# keyboard-Left.net
KiCad netlist of a schematic drawn in Altium Designer
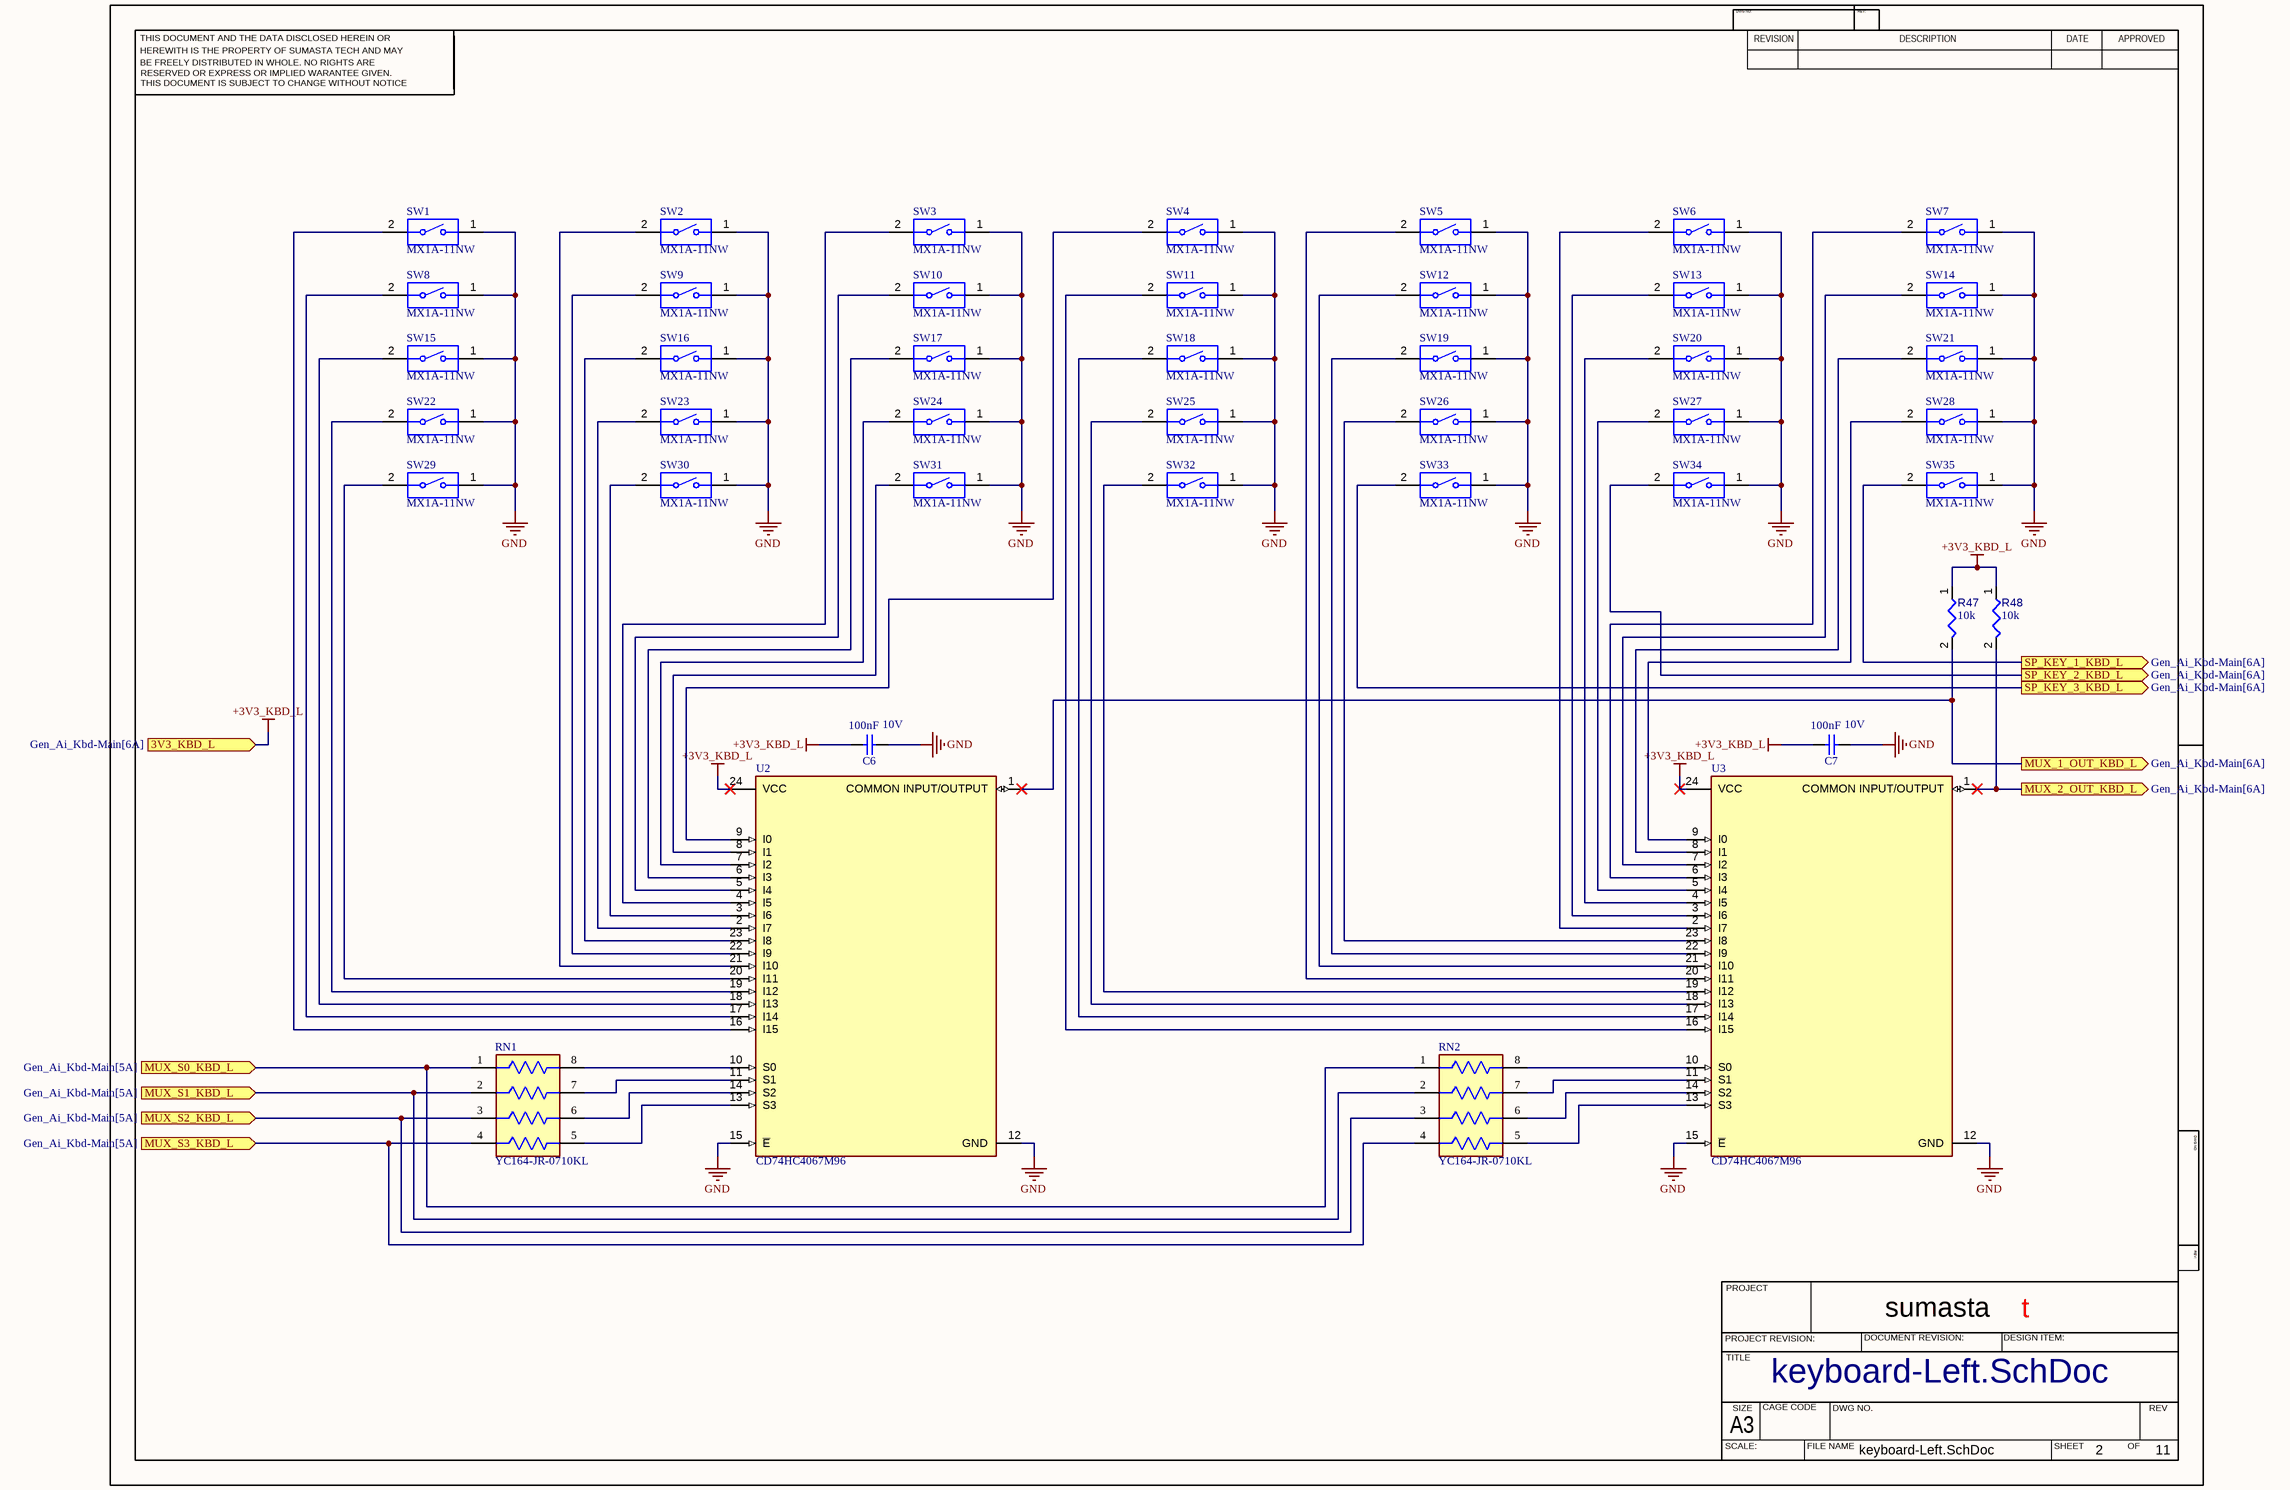
[diagram p0: keyboard-Left.SchDoc]

(export (version "E")
  (design (tool "Eeschema 10.0.6"))
  (components
    (comp (ref "C6")
      (value "885012206020")
      (footprint "WCAP-CSGP_0603_L1.6W0.8H0.8_Reflow")
      (description "WCAP-CSGP Multilayer Ceramic Chip Capacitor, General Purpose, size 0603, X7R, 100nF, 10VDC")
      (fields
        (field (name "MANUFACTURER") "Wurth Elektronik")
        (field (name "RATED VOLTAGE (DC)") "10V")
        (field (name "CAPACITANCE") "100nF")
      )
      (libsource (lib "Test365") (part "885012209047R"))
    )
    (comp (ref "C7")
      (value "885012206020")
      (footprint "WCAP-CSGP_0603_L1.6W0.8H0.8_Reflow")
      (description "WCAP-CSGP Multilayer Ceramic Chip Capacitor, General Purpose, size 0603, X7R, 100nF, 10VDC")
      (fields
        (field (name "MANUFACTURER") "Wurth Elektronik")
        (field (name "RATED VOLTAGE (DC)") "10V")
        (field (name "CAPACITANCE") "100nF")
      )
      (libsource (lib "Test365") (part "885012209047R"))
    )
    (comp (ref "R47")
      (value "10k")
      (footprint "RESC1608X55X25ML10T15")
      (description "Chip Resistor, 10 KOhm, +/- 1%, 01 W, -55 to 155 degC, 0603 (1608 Metric)")
      (fields (field (name "POWER") "100mW") (field (name "TOLERANCE") "1%"))
      (libsource (lib "Test365") (part "RES-2"))
    )
    (comp (ref "R48")
      (value "10k")
      (footprint "RESC1608X55X25ML10T15")
      (description "Chip Resistor, 10 KOhm, +/- 1%, 01 W, -55 to 155 degC, 0603 (1608 Metric)")
      (fields (field (name "POWER") "100mW") (field (name "TOLERANCE") "1%"))
      (libsource (lib "Test365") (part "RES-2"))
    )
    (comp (ref "RN1")
      (value "YC164-JR-0710KL")
      (footprint "FP-YC164-MFG")
      (description "RES ARRAY 4 RES 10K OHM 1206")
      (fields (field (name "TOLERANCE") "1%"))
      (libsource (lib "Altium Content Vault") (part "deefe693e103177f92eb02ee49083c3"))
    )
    (comp (ref "RN2")
      (value "YC164-JR-0710KL")
      (footprint "FP-YC164-MFG")
      (description "RES ARRAY 4 RES 10K OHM 1206")
      (fields (field (name "TOLERANCE") "1%"))
      (libsource (lib "Altium Content Vault") (part "deefe693e103177f92eb02ee49083c3"))
    )
    (comp (ref "SW1")
      (value "MX1A-11NW")
      (footprint "CHRY-MX1A-11NW_V")
      (description "Switch Key N.O. SPST 0.01A 12VAC 12VDC 0.58N PC Pins 50000000Cycles Thru-Hole")
      (libsource (lib "Test365") (part "KEYSW-SPST-2"))
    )
    (comp (ref "SW2")
      (value "MX1A-11NW")
      (footprint "CHRY-MX1A-11NW_V")
      (description "Switch Key N.O. SPST 0.01A 12VAC 12VDC 0.58N PC Pins 50000000Cycles Thru-Hole")
      (libsource (lib "Test365") (part "KEYSW-SPST-2"))
    )
    (comp (ref "SW3")
      (value "MX1A-11NW")
      (footprint "CHRY-MX1A-11NW_V")
      (description "Switch Key N.O. SPST 0.01A 12VAC 12VDC 0.58N PC Pins 50000000Cycles Thru-Hole")
      (libsource (lib "Test365") (part "KEYSW-SPST-2"))
    )
    (comp (ref "SW4")
      (value "MX1A-11NW")
      (footprint "CHRY-MX1A-11NW_V")
      (description "Switch Key N.O. SPST 0.01A 12VAC 12VDC 0.58N PC Pins 50000000Cycles Thru-Hole")
      (libsource (lib "Test365") (part "KEYSW-SPST-2"))
    )
    (comp (ref "SW5")
      (value "MX1A-11NW")
      (footprint "CHRY-MX1A-11NW_V")
      (description "Switch Key N.O. SPST 0.01A 12VAC 12VDC 0.58N PC Pins 50000000Cycles Thru-Hole")
      (libsource (lib "Test365") (part "KEYSW-SPST-2"))
    )
    (comp (ref "SW6")
      (value "MX1A-11NW")
      (footprint "CHRY-MX1A-11NW_V")
      (description "Switch Key N.O. SPST 0.01A 12VAC 12VDC 0.58N PC Pins 50000000Cycles Thru-Hole")
      (libsource (lib "Test365") (part "KEYSW-SPST-2"))
    )
    (comp (ref "SW7")
      (value "MX1A-11NW")
      (footprint "CHRY-MX1A-11NW_V")
      (description "Switch Key N.O. SPST 0.01A 12VAC 12VDC 0.58N PC Pins 50000000Cycles Thru-Hole")
      (libsource (lib "Test365") (part "KEYSW-SPST-2"))
    )
    (comp (ref "SW8")
      (value "MX1A-11NW")
      (footprint "CHRY-MX1A-11NW_V")
      (description "Switch Key N.O. SPST 0.01A 12VAC 12VDC 0.58N PC Pins 50000000Cycles Thru-Hole")
      (libsource (lib "Test365") (part "KEYSW-SPST-2"))
    )
    (comp (ref "SW9")
      (value "MX1A-11NW")
      (footprint "CHRY-MX1A-11NW_V")
      (description "Switch Key N.O. SPST 0.01A 12VAC 12VDC 0.58N PC Pins 50000000Cycles Thru-Hole")
      (libsource (lib "Test365") (part "KEYSW-SPST-2"))
    )
    (comp (ref "SW10")
      (value "MX1A-11NW")
      (footprint "CHRY-MX1A-11NW_V")
      (description "Switch Key N.O. SPST 0.01A 12VAC 12VDC 0.58N PC Pins 50000000Cycles Thru-Hole")
      (libsource (lib "Test365") (part "KEYSW-SPST-2"))
    )
    (comp (ref "SW11")
      (value "MX1A-11NW")
      (footprint "CHRY-MX1A-11NW_V")
      (description "Switch Key N.O. SPST 0.01A 12VAC 12VDC 0.58N PC Pins 50000000Cycles Thru-Hole")
      (libsource (lib "Test365") (part "KEYSW-SPST-2"))
    )
    (comp (ref "SW12")
      (value "MX1A-11NW")
      (footprint "CHRY-MX1A-11NW_V")
      (description "Switch Key N.O. SPST 0.01A 12VAC 12VDC 0.58N PC Pins 50000000Cycles Thru-Hole")
      (libsource (lib "Test365") (part "KEYSW-SPST-2"))
    )
    (comp (ref "SW13")
      (value "MX1A-11NW")
      (footprint "CHRY-MX1A-11NW_V")
      (description "Switch Key N.O. SPST 0.01A 12VAC 12VDC 0.58N PC Pins 50000000Cycles Thru-Hole")
      (libsource (lib "Test365") (part "KEYSW-SPST-2"))
    )
    (comp (ref "SW14")
      (value "MX1A-11NW")
      (footprint "CHRY-MX1A-11NW_V")
      (description "Switch Key N.O. SPST 0.01A 12VAC 12VDC 0.58N PC Pins 50000000Cycles Thru-Hole")
      (libsource (lib "Test365") (part "KEYSW-SPST-2"))
    )
    (comp (ref "SW15")
      (value "MX1A-11NW")
      (footprint "CHRY-MX1A-11NW_V")
      (description "Switch Key N.O. SPST 0.01A 12VAC 12VDC 0.58N PC Pins 50000000Cycles Thru-Hole")
      (libsource (lib "Test365") (part "KEYSW-SPST-2"))
    )
    (comp (ref "SW16")
      (value "MX1A-11NW")
      (footprint "CHRY-MX1A-11NW_V")
      (description "Switch Key N.O. SPST 0.01A 12VAC 12VDC 0.58N PC Pins 50000000Cycles Thru-Hole")
      (libsource (lib "Test365") (part "KEYSW-SPST-2"))
    )
    (comp (ref "SW17")
      (value "MX1A-11NW")
      (footprint "CHRY-MX1A-11NW_V")
      (description "Switch Key N.O. SPST 0.01A 12VAC 12VDC 0.58N PC Pins 50000000Cycles Thru-Hole")
      (libsource (lib "Test365") (part "KEYSW-SPST-2"))
    )
    (comp (ref "SW18")
      (value "MX1A-11NW")
      (footprint "CHRY-MX1A-11NW_V")
      (description "Switch Key N.O. SPST 0.01A 12VAC 12VDC 0.58N PC Pins 50000000Cycles Thru-Hole")
      (libsource (lib "Test365") (part "KEYSW-SPST-2"))
    )
    (comp (ref "SW19")
      (value "MX1A-11NW")
      (footprint "CHRY-MX1A-11NW_V")
      (description "Switch Key N.O. SPST 0.01A 12VAC 12VDC 0.58N PC Pins 50000000Cycles Thru-Hole")
      (libsource (lib "Test365") (part "KEYSW-SPST-2"))
    )
    (comp (ref "SW20")
      (value "MX1A-11NW")
      (footprint "CHRY-MX1A-11NW_V")
      (description "Switch Key N.O. SPST 0.01A 12VAC 12VDC 0.58N PC Pins 50000000Cycles Thru-Hole")
      (libsource (lib "Test365") (part "KEYSW-SPST-2"))
    )
    (comp (ref "SW21")
      (value "MX1A-11NW")
      (footprint "CHRY-MX1A-11NW_V")
      (description "Switch Key N.O. SPST 0.01A 12VAC 12VDC 0.58N PC Pins 50000000Cycles Thru-Hole")
      (libsource (lib "Test365") (part "KEYSW-SPST-2"))
    )
    (comp (ref "SW22")
      (value "MX1A-11NW")
      (footprint "CHRY-MX1A-11NW_V")
      (description "Switch Key N.O. SPST 0.01A 12VAC 12VDC 0.58N PC Pins 50000000Cycles Thru-Hole")
      (libsource (lib "Test365") (part "KEYSW-SPST-2"))
    )
    (comp (ref "SW23")
      (value "MX1A-11NW")
      (footprint "CHRY-MX1A-11NW_V")
      (description "Switch Key N.O. SPST 0.01A 12VAC 12VDC 0.58N PC Pins 50000000Cycles Thru-Hole")
      (libsource (lib "Test365") (part "KEYSW-SPST-2"))
    )
    (comp (ref "SW24")
      (value "MX1A-11NW")
      (footprint "CHRY-MX1A-11NW_V")
      (description "Switch Key N.O. SPST 0.01A 12VAC 12VDC 0.58N PC Pins 50000000Cycles Thru-Hole")
      (libsource (lib "Test365") (part "KEYSW-SPST-2"))
    )
    (comp (ref "SW25")
      (value "MX1A-11NW")
      (footprint "CHRY-MX1A-11NW_V")
      (description "Switch Key N.O. SPST 0.01A 12VAC 12VDC 0.58N PC Pins 50000000Cycles Thru-Hole")
      (libsource (lib "Test365") (part "KEYSW-SPST-2"))
    )
    (comp (ref "SW26")
      (value "MX1A-11NW")
      (footprint "CHRY-MX1A-11NW_V")
      (description "Switch Key N.O. SPST 0.01A 12VAC 12VDC 0.58N PC Pins 50000000Cycles Thru-Hole")
      (libsource (lib "Test365") (part "KEYSW-SPST-2"))
    )
    (comp (ref "SW27")
      (value "MX1A-11NW")
      (footprint "CHRY-MX1A-11NW_V")
      (description "Switch Key N.O. SPST 0.01A 12VAC 12VDC 0.58N PC Pins 50000000Cycles Thru-Hole")
      (libsource (lib "Test365") (part "KEYSW-SPST-2"))
    )
    (comp (ref "SW28")
      (value "MX1A-11NW")
      (footprint "CHRY-MX1A-11NW_V")
      (description "Switch Key N.O. SPST 0.01A 12VAC 12VDC 0.58N PC Pins 50000000Cycles Thru-Hole")
      (libsource (lib "Test365") (part "KEYSW-SPST-2"))
    )
    (comp (ref "SW29")
      (value "MX1A-11NW")
      (footprint "CHRY-MX1A-11NW_V")
      (description "Switch Key N.O. SPST 0.01A 12VAC 12VDC 0.58N PC Pins 50000000Cycles Thru-Hole")
      (libsource (lib "Test365") (part "KEYSW-SPST-2"))
    )
    (comp (ref "SW30")
      (value "MX1A-11NW")
      (footprint "CHRY-MX1A-11NW_V")
      (description "Switch Key N.O. SPST 0.01A 12VAC 12VDC 0.58N PC Pins 50000000Cycles Thru-Hole")
      (libsource (lib "Test365") (part "KEYSW-SPST-2"))
    )
    (comp (ref "SW31")
      (value "MX1A-11NW")
      (footprint "CHRY-MX1A-11NW_V")
      (description "Switch Key N.O. SPST 0.01A 12VAC 12VDC 0.58N PC Pins 50000000Cycles Thru-Hole")
      (libsource (lib "Test365") (part "KEYSW-SPST-2"))
    )
    (comp (ref "SW32")
      (value "MX1A-11NW")
      (footprint "CHRY-MX1A-11NW_V")
      (description "Switch Key N.O. SPST 0.01A 12VAC 12VDC 0.58N PC Pins 50000000Cycles Thru-Hole")
      (libsource (lib "Test365") (part "KEYSW-SPST-2"))
    )
    (comp (ref "SW33")
      (value "MX1A-11NW")
      (footprint "CHRY-MX1A-11NW_V")
      (description "Switch Key N.O. SPST 0.01A 12VAC 12VDC 0.58N PC Pins 50000000Cycles Thru-Hole")
      (libsource (lib "Test365") (part "KEYSW-SPST-2"))
    )
    (comp (ref "SW34")
      (value "MX1A-11NW")
      (footprint "CHRY-MX1A-11NW_V")
      (description "Switch Key N.O. SPST 0.01A 12VAC 12VDC 0.58N PC Pins 50000000Cycles Thru-Hole")
      (libsource (lib "Test365") (part "KEYSW-SPST-2"))
    )
    (comp (ref "SW35")
      (value "MX1A-11NW")
      (footprint "CHRY-MX1A-11NW_V")
      (description "Switch Key N.O. SPST 0.01A 12VAC 12VDC 0.58N PC Pins 50000000Cycles Thru-Hole")
      (libsource (lib "Test365") (part "KEYSW-SPST-2"))
    )
    (comp (ref "U2")
      (value "CD74HC4067M96")
      (footprint "FP-DW0024A-MFG")
      (description "IC MUX/DEMUX 1X16 24SOIC")
      (fields
        (field (name "OCTOPART") "https://octopart.com/cd74hc4067m96-texas+instruments-722802")
        (field (name "MANUFACTURER") "Texas Instruments")
      )
      (libsource (lib "Altium Content Vault") (part "0e3014a41e7f600214dac1b4fa06845"))
    )
    (comp (ref "U3")
      (value "CD74HC4067M96")
      (footprint "FP-DW0024A-MFG")
      (description "IC MUX/DEMUX 1X16 24SOIC")
      (fields
        (field (name "OCTOPART") "https://octopart.com/cd74hc4067m96-texas+instruments-722802")
        (field (name "MANUFACTURER") "Texas Instruments")
      )
      (libsource (lib "Altium Content Vault") (part "0e3014a41e7f600214dac1b4fa06845"))
    )
  )
  (nets
    (net (code "1") (name "+3V3_KBD_L") (class "Default")
      (node (ref "C6") (pin "1") (pinfunction "1_1") (pintype "passive"))
      (node (ref "C7") (pin "1") (pinfunction "1_1") (pintype "passive"))
      (node (ref "R47") (pin "1") (pinfunction "1_1") (pintype "passive"))
      (node (ref "R48") (pin "1") (pinfunction "1_1") (pintype "passive"))
      (node (ref "U2") (pin "24") (pinfunction "VCC_24") (pintype "power_in"))
      (node (ref "U3") (pin "24") (pinfunction "VCC_24") (pintype "power_in"))
    )
    (net (code "2") (name "/MUX_1_OUT_KBD_L") (class "Default")
      (node (ref "R47") (pin "2") (pinfunction "2_2") (pintype "passive"))
      (node (ref "U2") (pin "1") (pinfunction "COMMON_INPUT/OUTPUT_1") (pintype "bidirectional"))
    )
    (net (code "3") (name "/MUX_2_OUT_KBD_L") (class "Default")
      (node (ref "R48") (pin "2") (pinfunction "2_2") (pintype "passive"))
      (node (ref "U3") (pin "1") (pinfunction "COMMON_INPUT/OUTPUT_1") (pintype "bidirectional"))
    )
    (net (code "4") (name "/MUX_S0_KBD_L") (class "Default")
      (node (ref "RN1") (pin "1") (pinfunction "1_1") (pintype "passive"))
      (node (ref "RN2") (pin "1") (pinfunction "1_1") (pintype "passive"))
    )
    (net (code "5") (name "/MUX_S1_KBD_L") (class "Default")
      (node (ref "RN1") (pin "2") (pinfunction "2_2") (pintype "passive"))
      (node (ref "RN2") (pin "2") (pinfunction "2_2") (pintype "passive"))
    )
    (net (code "6") (name "/MUX_S2_KBD_L") (class "Default")
      (node (ref "RN1") (pin "3") (pinfunction "3_3") (pintype "passive"))
      (node (ref "RN2") (pin "3") (pinfunction "3_3") (pintype "passive"))
    )
    (net (code "7") (name "/MUX_S3_KBD_L") (class "Default")
      (node (ref "RN1") (pin "4") (pinfunction "4_4") (pintype "passive"))
      (node (ref "RN2") (pin "4") (pinfunction "4_4") (pintype "passive"))
    )
    (net (code "8") (name "/SP_KEY_1_KBD_L") (class "Default")
      (node (ref "SW35") (pin "2") (pinfunction "2_2") (pintype "passive"))
    )
    (net (code "9") (name "/SP_KEY_2_KBD_L") (class "Default")
      (node (ref "SW34") (pin "2") (pinfunction "2_2") (pintype "passive"))
    )
    (net (code "10") (name "/SP_KEY_3_KBD_L") (class "Default")
      (node (ref "SW33") (pin "2") (pinfunction "2_2") (pintype "passive"))
    )
    (net (code "11") (name "GND") (class "Default")
      (node (ref "C6") (pin "2") (pinfunction "2_2") (pintype "passive"))
      (node (ref "C7") (pin "2") (pinfunction "2_2") (pintype "passive"))
      (node (ref "SW1") (pin "1") (pinfunction "1_1") (pintype "passive"))
      (node (ref "SW10") (pin "1") (pinfunction "1_1") (pintype "passive"))
      (node (ref "SW11") (pin "1") (pinfunction "1_1") (pintype "passive"))
      (node (ref "SW12") (pin "1") (pinfunction "1_1") (pintype "passive"))
      (node (ref "SW13") (pin "1") (pinfunction "1_1") (pintype "passive"))
      (node (ref "SW14") (pin "1") (pinfunction "1_1") (pintype "passive"))
      (node (ref "SW15") (pin "1") (pinfunction "1_1") (pintype "passive"))
      (node (ref "SW16") (pin "1") (pinfunction "1_1") (pintype "passive"))
      (node (ref "SW17") (pin "1") (pinfunction "1_1") (pintype "passive"))
      (node (ref "SW18") (pin "1") (pinfunction "1_1") (pintype "passive"))
      (node (ref "SW19") (pin "1") (pinfunction "1_1") (pintype "passive"))
      (node (ref "SW2") (pin "1") (pinfunction "1_1") (pintype "passive"))
      (node (ref "SW20") (pin "1") (pinfunction "1_1") (pintype "passive"))
      (node (ref "SW21") (pin "1") (pinfunction "1_1") (pintype "passive"))
      (node (ref "SW22") (pin "1") (pinfunction "1_1") (pintype "passive"))
      (node (ref "SW23") (pin "1") (pinfunction "1_1") (pintype "passive"))
      (node (ref "SW24") (pin "1") (pinfunction "1_1") (pintype "passive"))
      (node (ref "SW25") (pin "1") (pinfunction "1_1") (pintype "passive"))
      (node (ref "SW26") (pin "1") (pinfunction "1_1") (pintype "passive"))
      (node (ref "SW27") (pin "1") (pinfunction "1_1") (pintype "passive"))
      (node (ref "SW28") (pin "1") (pinfunction "1_1") (pintype "passive"))
      (node (ref "SW29") (pin "1") (pinfunction "1_1") (pintype "passive"))
      (node (ref "SW3") (pin "1") (pinfunction "1_1") (pintype "passive"))
      (node (ref "SW30") (pin "1") (pinfunction "1_1") (pintype "passive"))
      (node (ref "SW31") (pin "1") (pinfunction "1_1") (pintype "passive"))
      (node (ref "SW32") (pin "1") (pinfunction "1_1") (pintype "passive"))
      (node (ref "SW33") (pin "1") (pinfunction "1_1") (pintype "passive"))
      (node (ref "SW34") (pin "1") (pinfunction "1_1") (pintype "passive"))
      (node (ref "SW35") (pin "1") (pinfunction "1_1") (pintype "passive"))
      (node (ref "SW4") (pin "1") (pinfunction "1_1") (pintype "passive"))
      (node (ref "SW5") (pin "1") (pinfunction "1_1") (pintype "passive"))
      (node (ref "SW6") (pin "1") (pinfunction "1_1") (pintype "passive"))
      (node (ref "SW7") (pin "1") (pinfunction "1_1") (pintype "passive"))
      (node (ref "SW8") (pin "1") (pinfunction "1_1") (pintype "passive"))
      (node (ref "SW9") (pin "1") (pinfunction "1_1") (pintype "passive"))
      (node (ref "U2") (pin "12") (pinfunction "GND_12") (pintype "power_in"))
      (node (ref "U2") (pin "15") (pinfunction "~{E}_15") (pintype "input"))
      (node (ref "U3") (pin "12") (pinfunction "GND_12") (pintype "power_in"))
      (node (ref "U3") (pin "15") (pinfunction "~{E}_15") (pintype "input"))
    )
    (net (code "12") (name "Net-(U2-I0)") (class "Default")
      (node (ref "SW4") (pin "2") (pinfunction "2_2") (pintype "passive"))
      (node (ref "U2") (pin "9") (pinfunction "I0_9") (pintype "input"))
    )
    (net (code "13") (name "Net-(U2-I1)") (class "Default")
      (node (ref "SW31") (pin "2") (pinfunction "2_2") (pintype "passive"))
      (node (ref "U2") (pin "8") (pinfunction "I1_8") (pintype "input"))
    )
    (net (code "14") (name "Net-(U2-I2)") (class "Default")
      (node (ref "SW24") (pin "2") (pinfunction "2_2") (pintype "passive"))
      (node (ref "U2") (pin "7") (pinfunction "I2_7") (pintype "input"))
    )
    (net (code "15") (name "Net-(U2-I3)") (class "Default")
      (node (ref "SW17") (pin "2") (pinfunction "2_2") (pintype "passive"))
      (node (ref "U2") (pin "6") (pinfunction "I3_6") (pintype "input"))
    )
    (net (code "16") (name "Net-(U2-I4)") (class "Default")
      (node (ref "SW10") (pin "2") (pinfunction "2_2") (pintype "passive"))
      (node (ref "U2") (pin "5") (pinfunction "I4_5") (pintype "input"))
    )
    (net (code "17") (name "Net-(U2-I5)") (class "Default")
      (node (ref "SW3") (pin "2") (pinfunction "2_2") (pintype "passive"))
      (node (ref "U2") (pin "4") (pinfunction "I5_4") (pintype "input"))
    )
    (net (code "18") (name "Net-(U2-I6)") (class "Default")
      (node (ref "SW30") (pin "2") (pinfunction "2_2") (pintype "passive"))
      (node (ref "U2") (pin "3") (pinfunction "I6_3") (pintype "input"))
    )
    (net (code "19") (name "Net-(U2-I7)") (class "Default")
      (node (ref "SW23") (pin "2") (pinfunction "2_2") (pintype "passive"))
      (node (ref "U2") (pin "2") (pinfunction "I7_2") (pintype "input"))
    )
    (net (code "20") (name "Net-(U2-I8)") (class "Default")
      (node (ref "SW16") (pin "2") (pinfunction "2_2") (pintype "passive"))
      (node (ref "U2") (pin "23") (pinfunction "I8_23") (pintype "input"))
    )
    (net (code "21") (name "Net-(U2-I9)") (class "Default")
      (node (ref "SW9") (pin "2") (pinfunction "2_2") (pintype "passive"))
      (node (ref "U2") (pin "22") (pinfunction "I9_22") (pintype "input"))
    )
    (net (code "22") (name "Net-(U2-I10)") (class "Default")
      (node (ref "SW2") (pin "2") (pinfunction "2_2") (pintype "passive"))
      (node (ref "U2") (pin "21") (pinfunction "I10_21") (pintype "input"))
    )
    (net (code "23") (name "Net-(U2-I11)") (class "Default")
      (node (ref "SW29") (pin "2") (pinfunction "2_2") (pintype "passive"))
      (node (ref "U2") (pin "20") (pinfunction "I11_20") (pintype "input"))
    )
    (net (code "24") (name "Net-(U2-I12)") (class "Default")
      (node (ref "SW22") (pin "2") (pinfunction "2_2") (pintype "passive"))
      (node (ref "U2") (pin "19") (pinfunction "I12_19") (pintype "input"))
    )
    (net (code "25") (name "Net-(U2-I13)") (class "Default")
      (node (ref "SW15") (pin "2") (pinfunction "2_2") (pintype "passive"))
      (node (ref "U2") (pin "18") (pinfunction "I13_18") (pintype "input"))
    )
    (net (code "26") (name "Net-(U2-I14)") (class "Default")
      (node (ref "SW8") (pin "2") (pinfunction "2_2") (pintype "passive"))
      (node (ref "U2") (pin "17") (pinfunction "I14_17") (pintype "input"))
    )
    (net (code "27") (name "Net-(U2-I15)") (class "Default")
      (node (ref "SW1") (pin "2") (pinfunction "2_2") (pintype "passive"))
      (node (ref "U2") (pin "16") (pinfunction "I15_16") (pintype "input"))
    )
    (net (code "28") (name "Net-(U2-S0)") (class "Default")
      (node (ref "RN1") (pin "8") (pinfunction "8_8") (pintype "passive"))
      (node (ref "U2") (pin "10") (pinfunction "S0_10") (pintype "input"))
    )
    (net (code "29") (name "Net-(U2-S1)") (class "Default")
      (node (ref "RN1") (pin "7") (pinfunction "7_7") (pintype "passive"))
      (node (ref "U2") (pin "11") (pinfunction "S1_11") (pintype "input"))
    )
    (net (code "30") (name "Net-(U2-S2)") (class "Default")
      (node (ref "RN1") (pin "6") (pinfunction "6_6") (pintype "passive"))
      (node (ref "U2") (pin "14") (pinfunction "S2_14") (pintype "input"))
    )
    (net (code "31") (name "Net-(U2-S3)") (class "Default")
      (node (ref "RN1") (pin "5") (pinfunction "5_5") (pintype "passive"))
      (node (ref "U2") (pin "13") (pinfunction "S3_13") (pintype "input"))
    )
    (net (code "32") (name "Net-(U3-I0)") (class "Default")
      (node (ref "SW28") (pin "2") (pinfunction "2_2") (pintype "passive"))
      (node (ref "U3") (pin "9") (pinfunction "I0_9") (pintype "input"))
    )
    (net (code "33") (name "Net-(U3-I1)") (class "Default")
      (node (ref "SW21") (pin "2") (pinfunction "2_2") (pintype "passive"))
      (node (ref "U3") (pin "8") (pinfunction "I1_8") (pintype "input"))
    )
    (net (code "34") (name "Net-(U3-I2)") (class "Default")
      (node (ref "SW14") (pin "2") (pinfunction "2_2") (pintype "passive"))
      (node (ref "U3") (pin "7") (pinfunction "I2_7") (pintype "input"))
    )
    (net (code "35") (name "Net-(U3-I3)") (class "Default")
      (node (ref "SW7") (pin "2") (pinfunction "2_2") (pintype "passive"))
      (node (ref "U3") (pin "6") (pinfunction "I3_6") (pintype "input"))
    )
    (net (code "36") (name "Net-(U3-I4)") (class "Default")
      (node (ref "SW27") (pin "2") (pinfunction "2_2") (pintype "passive"))
      (node (ref "U3") (pin "5") (pinfunction "I4_5") (pintype "input"))
    )
    (net (code "37") (name "Net-(U3-I5)") (class "Default")
      (node (ref "SW20") (pin "2") (pinfunction "2_2") (pintype "passive"))
      (node (ref "U3") (pin "4") (pinfunction "I5_4") (pintype "input"))
    )
    (net (code "38") (name "Net-(U3-I6)") (class "Default")
      (node (ref "SW13") (pin "2") (pinfunction "2_2") (pintype "passive"))
      (node (ref "U3") (pin "3") (pinfunction "I6_3") (pintype "input"))
    )
    (net (code "39") (name "Net-(U3-I7)") (class "Default")
      (node (ref "SW6") (pin "2") (pinfunction "2_2") (pintype "passive"))
      (node (ref "U3") (pin "2") (pinfunction "I7_2") (pintype "input"))
    )
    (net (code "40") (name "Net-(U3-I8)") (class "Default")
      (node (ref "SW26") (pin "2") (pinfunction "2_2") (pintype "passive"))
      (node (ref "U3") (pin "23") (pinfunction "I8_23") (pintype "input"))
    )
    (net (code "41") (name "Net-(U3-I9)") (class "Default")
      (node (ref "SW19") (pin "2") (pinfunction "2_2") (pintype "passive"))
      (node (ref "U3") (pin "22") (pinfunction "I9_22") (pintype "input"))
    )
    (net (code "42") (name "Net-(U3-I10)") (class "Default")
      (node (ref "SW12") (pin "2") (pinfunction "2_2") (pintype "passive"))
      (node (ref "U3") (pin "21") (pinfunction "I10_21") (pintype "input"))
    )
    (net (code "43") (name "Net-(U3-I11)") (class "Default")
      (node (ref "SW5") (pin "2") (pinfunction "2_2") (pintype "passive"))
      (node (ref "U3") (pin "20") (pinfunction "I11_20") (pintype "input"))
    )
    (net (code "44") (name "Net-(U3-I12)") (class "Default")
      (node (ref "SW32") (pin "2") (pinfunction "2_2") (pintype "passive"))
      (node (ref "U3") (pin "19") (pinfunction "I12_19") (pintype "input"))
    )
    (net (code "45") (name "Net-(U3-I13)") (class "Default")
      (node (ref "SW25") (pin "2") (pinfunction "2_2") (pintype "passive"))
      (node (ref "U3") (pin "18") (pinfunction "I13_18") (pintype "input"))
    )
    (net (code "46") (name "Net-(U3-I14)") (class "Default")
      (node (ref "SW18") (pin "2") (pinfunction "2_2") (pintype "passive"))
      (node (ref "U3") (pin "17") (pinfunction "I14_17") (pintype "input"))
    )
    (net (code "47") (name "Net-(U3-I15)") (class "Default")
      (node (ref "SW11") (pin "2") (pinfunction "2_2") (pintype "passive"))
      (node (ref "U3") (pin "16") (pinfunction "I15_16") (pintype "input"))
    )
    (net (code "48") (name "Net-(U3-S0)") (class "Default")
      (node (ref "RN2") (pin "8") (pinfunction "8_8") (pintype "passive"))
      (node (ref "U3") (pin "10") (pinfunction "S0_10") (pintype "input"))
    )
    (net (code "49") (name "Net-(U3-S1)") (class "Default")
      (node (ref "RN2") (pin "7") (pinfunction "7_7") (pintype "passive"))
      (node (ref "U3") (pin "11") (pinfunction "S1_11") (pintype "input"))
    )
    (net (code "50") (name "Net-(U3-S2)") (class "Default")
      (node (ref "RN2") (pin "6") (pinfunction "6_6") (pintype "passive"))
      (node (ref "U3") (pin "14") (pinfunction "S2_14") (pintype "input"))
    )
    (net (code "51") (name "Net-(U3-S3)") (class "Default")
      (node (ref "RN2") (pin "5") (pinfunction "5_5") (pintype "passive"))
      (node (ref "U3") (pin "13") (pinfunction "S3_13") (pintype "input"))
    )
  )
)
